# Power.net
KiCad netlist of a schematic drawn in Altium Designer
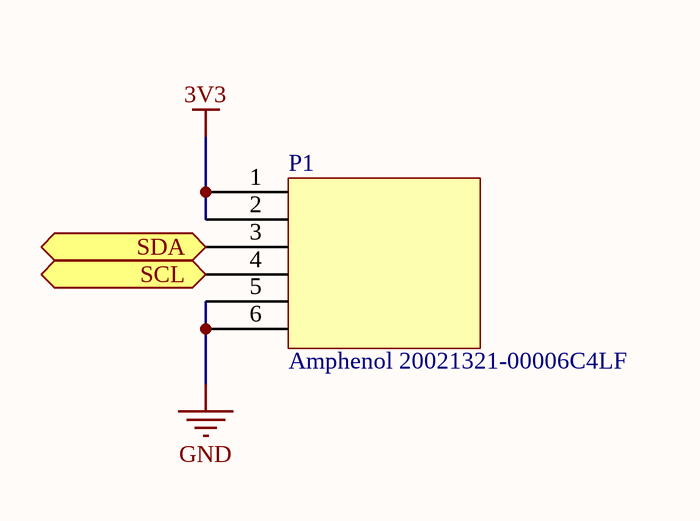
[diagram p0: Power.SchDoc]

(export (version "E")
  (design (tool "Eeschema 10.0.6"))
  (components
    (comp (ref "P1")
      (value "Amphenol 20021321-00006C4LF")
      (footprint "Amphenol FCI 20021321-00006C4LF - duplicate")
      (description "6 Position Receptacle Connector 0.050\" (1.27mm) Surface Mount Gold")
      (libsource (lib "SubjuGator8") (part "Amphenol FCI 20021321-00006C4LF"))
    )
  )
  (nets
    (net (code "1") (name "/SCL") (class "Default") (node (ref "P1") (pin "4") (pintype "passive")))
    (net (code "2") (name "/SDA") (class "Default") (node (ref "P1") (pin "3") (pintype "passive")))
    (net (code "3") (name "3V3") (class "Default")
      (node (ref "P1") (pin "1") (pintype "passive"))
      (node (ref "P1") (pin "2") (pintype "passive"))
    )
    (net (code "4") (name "GND") (class "Default")
      (node (ref "P1") (pin "5") (pintype "passive"))
      (node (ref "P1") (pin "6") (pintype "passive"))
    )
  )
)
